# EFR32G13_POWER_RESET.net
KiCad netlist of a schematic drawn in Altium Designer
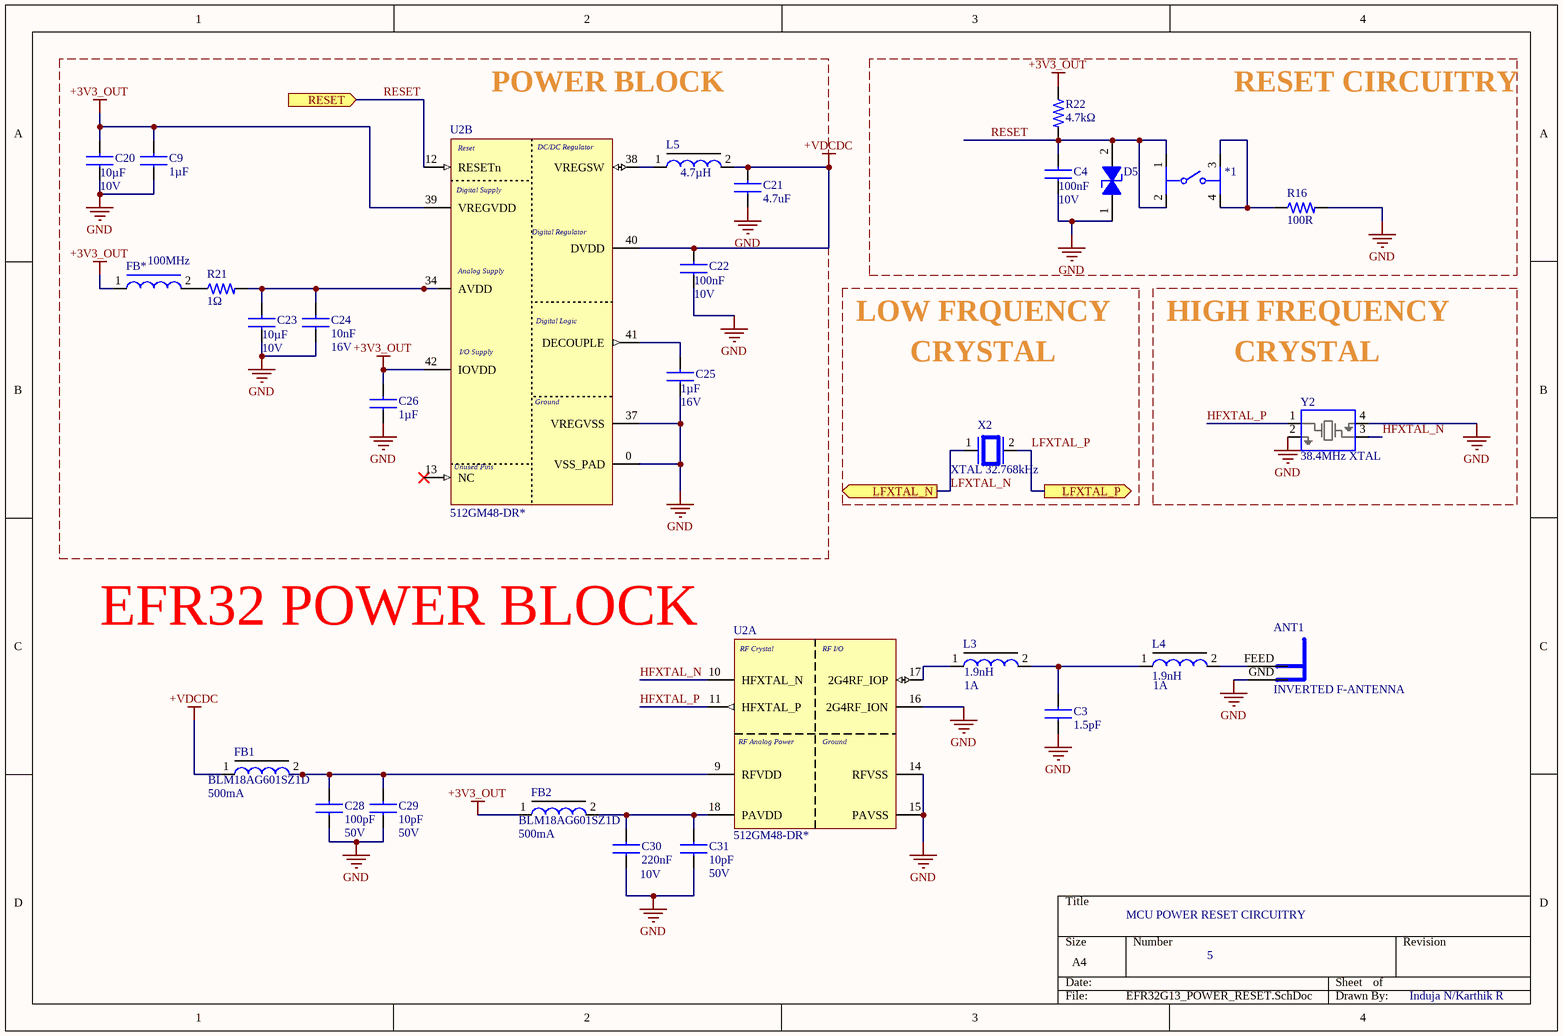
[diagram p0: EFR32G13_POWER_RESET.SchDoc]

(export (version "E")
  (design (tool "Eeschema 10.0.6"))
  (components
    (comp (ref "*1")
      (value "~")
      (footprint "SWITCH")
      (description "Switch Tactile SPST N.O. 0.05A 12VDC 200000Cycles Gull Wing Surface Mount T/R")
      (fields
        (field (name "MANUFACTURER") "C&K Components")
        (field (name "MANUFACTURER PART NUMBER") "PTS526 SK15 SMTR2 LFS")
      )
      (libsource (lib "LPEDT_Components") (part "PTS526 SK15 SMTR2 LFS"))
    )
    (comp (ref "ANT1")
      (value "INVERTED F-ANTENNA")
      (footprint "F_ANTENNA")
      (libsource (lib "LPEDT_Components") (part "INVERTED F-ANTENNA"))
    )
    (comp (ref "C3")
      (value "1.5pF")
      (footprint "Capacitor 0402")
      (fields
        (field (name "MANUFACTURER") "Murata")
        (field (name "MANUFACTURER PART NUMBER") "GJM1555C1H1R5WB01D")
        (field (name "Comment") "CAP 1.5pF 50V 0402")
      )
      (libsource (lib "LPEDT_Components") (part "CAP 1.5pF 50V 0402"))
    )
    (comp (ref "C4")
      (value "100nF")
      (footprint "CAP_0603_1MM")
      (description "0603 0.1 uF 10 V ±10% Tolerance X7R SMT Multilayer Ceramic Chip Capacitor")
      (fields
        (field (name "MANUFACTURER") "Vishay")
        (field (name "MANUFACTURER PART NUMBER") "VJ0603Y104KXQCW1BC")
        (field (name "VOLTAGE RATING (DC)") "10V")
      )
      (libsource (lib "LPEDT_Components") (part "CAP 0.1uF 0603"))
    )
    (comp (ref "C9")
      (value "1µF")
      (footprint "Capacitor 0603")
      (description "16V 1uF X7R ±10% 0603 Multilayer Ceramic Capacitors MLCC - SMD/SMT ROHS")
      (fields
        (field (name "MANUFACTURER") "Samsung Electro-Mechanics")
        (field (name "MANUFACTURER PART NUMBER") "CL10B105KO8NNNC")
      )
      (libsource (lib "LPEDT_Components") (part "CAP 1uF 0603"))
    )
    (comp (ref "C20")
      (value "10µF")
      (footprint "CAP_0603_1MM")
      (description "10V 10uF X7R ±10% 0603 Multilayer Ceramic Capacitors MLCC - SMD/SMT ROHS")
      (fields
        (field (name "MANUFACTURER") "Murata")
        (field (name "MANUFACTURER PART NUMBER") "GRM188Z71A106KA73D")
        (field (name "VOLTAGE RATING") "10V")
      )
      (libsource (lib "LPEDT_Components") (part "CAP 10uF 0603"))
    )
    (comp (ref "C21")
      (value "4.7uF")
      (footprint "CAPC1608X90N")
      (description "4.7 ÂµF Â±10% 16V Ceramic Capacitor X5R 0603 (1608 Metric)")
      (fields (field (name "MF") "Samsung Electro-Mechanics") (field (name "MP") "CL10A475KO8NNNC"))
      (libsource (lib "LPEDT_Components") (part "CAP 4.7uF 16V 0603"))
    )
    (comp (ref "C22")
      (value "100nF")
      (footprint "CAP_0603_1MM")
      (description "0603 0.1 uF 10 V ±10% Tolerance X7R SMT Multilayer Ceramic Chip Capacitor")
      (fields
        (field (name "MANUFACTURER") "Vishay")
        (field (name "MANUFACTURER PART NUMBER") "VJ0603Y104KXQCW1BC")
        (field (name "VOLTAGE RATING (DC)") "10V")
      )
      (libsource (lib "LPEDT_Components") (part "CAP 0.1uF 0603"))
    )
    (comp (ref "C23")
      (value "10µF")
      (footprint "CAP_0603_1MM")
      (description "10V 10uF X7R ±10% 0603 Multilayer Ceramic Capacitors MLCC - SMD/SMT ROHS")
      (fields
        (field (name "MANUFACTURER") "Murata")
        (field (name "MANUFACTURER PART NUMBER") "GRM188Z71A106KA73D")
        (field (name "VOLTAGE RATING") "10V")
      )
      (libsource (lib "LPEDT_Components") (part "CAP 10uF 0603"))
    )
    (comp (ref "C24")
      (value "10nF")
      (footprint "Capacitor 0603")
      (description "Multilayer Ceramic Capacitors MLCC - SMD/SMT 16V 0.01uF X7R 0603 10% AEC-Q200")
      (fields
        (field (name "MANUFACTURER") "KEMET")
        (field (name "MANUFACTURER PART NUMBER") "C0603C103K4RECAUTO")
        (field (name "VOLTAGE RATING (DC)") "16V")
      )
      (libsource (lib "LPEDT_Components") (part "CAP 10nF 0603"))
    )
    (comp (ref "C25")
      (value "1µF")
      (footprint "Capacitor 0603")
      (description "16V 1uF X7R ±10% 0603 Multilayer Ceramic Capacitors MLCC - SMD/SMT ROHS")
      (fields
        (field (name "MANUFACTURER") "Samsung Electro-Mechanics")
        (field (name "MANUFACTURER PART NUMBER") "CL10B105KO8NNNC")
        (field (name "VOLTAGE RATING (DC)") "16V")
      )
      (libsource (lib "LPEDT_Components") (part "CAP 1uF 0603"))
    )
    (comp (ref "C26")
      (value "1µF")
      (footprint "Capacitor 0603")
      (description "16V 1uF X7R ±10% 0603 Multilayer Ceramic Capacitors MLCC - SMD/SMT ROHS")
      (fields
        (field (name "MANUFACTURER") "Samsung Electro-Mechanics")
        (field (name "MANUFACTURER PART NUMBER") "CL10B105KO8NNNC")
      )
      (libsource (lib "LPEDT_Components") (part "CAP 1uF 0603"))
    )
    (comp (ref "C28")
      (value "100pF")
      (footprint "CAP_0603_1MM")
      (description "50V 100pF NP0 ±5% 0603 Multilayer Ceramic Capacitors MLCC - SMD/SMT ROHS")
      (fields
        (field (name "MANUFACTURER") "Yageo Group")
        (field (name "MANUFACTURER PART NUMBER") "CC0603JRNPO9BN101")
        (field (name "VOLTAGE RATING (DC)") "50V")
      )
      (libsource (lib "LPEDT_Components") (part "CAP 100pF 0603"))
    )
    (comp (ref "C29")
      (value "10pF")
      (footprint "Capacitor 0603")
      (fields
        (field (name "MANUFACTURER") "Murata")
        (field (name "MANUFACTURER PART NUMBER") "GRM1555C1H100FA01D")
        (field (name "RATED DC VOLTAGE (URDC)") "50V")
        (field (name "Comment") "CAP 10pF 50V 0603")
      )
      (libsource (lib "LPEDT_Components") (part "CAP 10pF 50V 0603"))
    )
    (comp (ref "C30")
      (value "220nF")
      (footprint "Capacitor 0603")
      (description "0603 0.22 uF 10 V ±10% Tolerance X7R SMT Multilayer Ceramic Capacitor")
      (fields
        (field (name "MANUFACTURER") "Murata")
        (field (name "MANUFACTURER PART NUMBER") "GRM188R71A224KA01J")
        (field (name "VOLTAGE RATING") "10V")
      )
      (libsource (lib "LPEDT_Components") (part "CAP 220nF 10V 0603"))
    )
    (comp (ref "C31")
      (value "10pF")
      (footprint "Capacitor 0603")
      (fields
        (field (name "MANUFACTURER") "Murata")
        (field (name "MANUFACTURER PART NUMBER") "GRM1555C1H100FA01D")
        (field (name "RATED DC VOLTAGE (URDC)") "50V")
        (field (name "Comment") "CAP 10pF 50V 0603")
      )
      (libsource (lib "LPEDT_Components") (part "CAP 10pF 50V 0603"))
    )
    (comp (ref "D5")
      (value "824032815")
      (footprint "WE-TVS_DFN1610-2L")
      (description "824032815 Tvs Diode, Bidir, 5V, Dfn1610 Rohs Compliant: Yes ¦Wurth Elektronik 824032815")
      (libsource (lib "LPEDT_Components") (part "TVS Diode ESD Protection"))
    )
    (comp (ref "FB*")
      (value "BLM21BD102SN1D")
      (footprint "FP-BLM21-0_2-t0_85-e0_5-IPC_A")
      (description "Ferrite Beads Multi-Layer 1KOhm 25% 100MHz 250mA 400mOhm DCR 0805 T/R")
      (fields
        (field (name "MANUFACTURER") "Murata")
        (field (name "CLOCK FREQUENCY") "100MHz")
        (field (name "TOLERANCE") "25%")
      )
      (libsource (lib "LPEDT_Components") (part "BLM21BD102SN1D"))
    )
    (comp (ref "FB1")
      (value "BLM18AG601SZ1D")
      (footprint "Ferrite 0603")
      (description "Chip Ferrite Bead, 0603, 600Ω @ 100MHz, 0.38Ω, 25%, 500mA CMP-06046-002436-1")
      (fields (field (name "MAX CURRENT RATING") "500mA"))
      (libsource (lib "LPEDT_Components") (part "600R Ferrite bead"))
    )
    (comp (ref "FB2")
      (value "BLM18AG601SZ1D")
      (footprint "Ferrite 0603")
      (description "Chip Ferrite Bead, 0603, 600Ω @ 100MHz, 0.38Ω, 25%, 500mA CMP-06046-002436-1")
      (fields (field (name "MAX CURRENT RATING") "500mA"))
      (libsource (lib "LPEDT_Components") (part "600R Ferrite bead"))
    )
    (comp (ref "L3")
      (value "1.9nH")
      (footprint "Ferrite 0402")
      (description "Inductor, 1.9Nh, 8Ghz, 0402 Rohs Compliant: Yes ¦Murata LQG15WZ1N9S02D")
      (fields
        (field (name "MANUFACTURER") "Murata")
        (field (name "MANUFACTURER PART NUMBER") "LQG15WZ1N9S02D")
        (field (name "CURRENT RATING") "1A")
      )
      (libsource (lib "LPEDT_Components") (part "IND 1.9nH"))
    )
    (comp (ref "L4")
      (value "1.9nH")
      (footprint "Ferrite 0402")
      (description "Inductor, 1.9Nh, 8Ghz, 0402 Rohs Compliant: Yes ¦Murata LQG15WZ1N9S02D")
      (fields
        (field (name "MANUFACTURER") "Murata")
        (field (name "MANUFACTURER PART NUMBER") "LQG15WZ1N9S02D")
        (field (name "CURRENT RATING") "1A")
      )
      (libsource (lib "LPEDT_Components") (part "IND 1.9nH"))
    )
    (comp (ref "L5")
      (value "4.7µH")
      (footprint "Capacitor 0603")
      (description "Inductor Power Shielded Multi-Layer 4.7uH 20% 2MHz Ferrite 0.12A 0.65Ohm DCR 0603 T/R")
      (fields
        (field (name "MANUFACTURER") "TDK")
        (field (name "MANUFACTURER PART NUMBER") "MLZ1608M4R7WT000")
      )
      (libsource (lib "LPEDT_Components") (part "IND 4.7uH"))
    )
    (comp (ref "R16")
      (value "100R")
      (footprint "RES_0603_1608X06")
      (fields
        (field (name "MANUFACTURER") "Yageo")
        (field (name "MANUFACTURER PART NUMBER") "RC0603FR-07100RL")
        (field (name "TOLERANCE") "1%")
      )
      (libsource (lib "LPEDT_Components") (part "RES 100R 0603"))
    )
    (comp (ref "R21")
      (value "1Ω")
      (footprint "RES_0603_1608X06")
      (fields
        (field (name "MANUFACTURER") "Yageo")
        (field (name "MANUFACTURER PART NUMBER") "RC0603FR-074K7L")
        (field (name "TOLERANCE") "1%")
      )
      (libsource (lib "LPEDT_Components") (part "RES 1Ohm 0603"))
    )
    (comp (ref "R22")
      (value "4.7kΩ")
      (footprint "RES_0603_1608X06")
      (fields
        (field (name "MANUFACTURER") "Yageo")
        (field (name "MANUFACTURER PART NUMBER") "RC0603FR-074K7L")
        (field (name "TOLERANCE") "1%")
      )
      (libsource (lib "LPEDT_Components") (part "RES 4.7K 0603"))
    )
    (comp (ref "U2")
      (value "512GM48-DR*")
      (footprint "QFN_48_7x7")
      (description "Blue Gecko QFN48 2.4 G 19 dB BLE/Proprietary 512 kB 64 kB(RAM) 31GPIO")
      (fields
        (field (name "MANUFACTURER") "Silicon Labs")
        (field (name "MANUFACTURER PART NUMBER") "EFR32BG13P732F512GM48-DR")
      )
      (libsource (lib "LPEDT_Components") (part "EFR32BG13P732F512GM48-DR"))
    )
    (comp (ref "X2")
      (value "XTAL 32.768kHz")
      (footprint "XTAL_32.768KHZ-T")
      (description "Crystal 0.032768MHz ±20ppm (Tol) 12.5pF Flexural 70000Ohm 2-Pin CSMD T/R")
      (fields
        (field (name "MANUFACTURER") "Abracon")
        (field (name "MANUFACTURER PART NUMBER") "ABS07-32.768KHZ-H-T")
      )
      (libsource (lib "LPEDT_Components") (part "XTAL 32.768kHz"))
    )
    (comp (ref "Y2")
      (value "38.4MHz XTAL")
      (footprint "XTAL 38.4MHz")
      (description "Fundamental Active RoHS Compliant MHz Crystal Crystal 10pF 0.022 0.55mm -20C~70C 80Ohm")
      (fields (field (name "MANUFACTURER") "TXC") (field (name "MANUFACTURER PART NUMBER") "8Y38472012"))
      (libsource (lib "LPEDT_Components") (part "38.4MHz XTAL"))
    )
  )
  (nets
    (net (code "1") (name "+3V3_OUT") (class "Default")
      (node (ref "C20") (pin "1") (pinfunction "1_1") (pintype "passive"))
      (node (ref "C26") (pin "1") (pinfunction "1_1") (pintype "passive"))
      (node (ref "C9") (pin "1") (pinfunction "1_1") (pintype "passive"))
      (node (ref "FB*") (pin "1") (pinfunction "1_1") (pintype "passive"))
      (node (ref "FB2") (pin "1") (pinfunction "1_1") (pintype "passive"))
      (node (ref "R22") (pin "1") (pinfunction "1_1") (pintype "passive"))
      (node (ref "U2") (pin "39") (pinfunction "VREGVDD_39") (pintype "power_in"))
      (node (ref "U2") (pin "42") (pinfunction "IOVDD_42") (pintype "power_in"))
    )
    (net (code "2") (name "+VDCDC") (class "Default")
      (node (ref "C21") (pin "1") (pinfunction "1_1") (pintype "passive"))
      (node (ref "C22") (pin "1") (pinfunction "1_1") (pintype "passive"))
      (node (ref "FB1") (pin "1") (pinfunction "1_1") (pintype "passive"))
      (node (ref "L5") (pin "2") (pinfunction "2_2") (pintype "passive"))
      (node (ref "U2") (pin "40") (pinfunction "DVDD_40") (pintype "power_in"))
    )
    (net (code "3") (name "/HFXTAL_N") (class "Default")
      (node (ref "U2") (pin "10") (pinfunction "HFXTAL_N_10") (pintype "input"))
      (node (ref "Y2") (pin "3") (pinfunction "3_3") (pintype "passive"))
    )
    (net (code "4") (name "/HFXTAL_P") (class "Default")
      (node (ref "U2") (pin "11") (pinfunction "HFXTAL_P_11") (pintype "output"))
      (node (ref "Y2") (pin "1") (pinfunction "1_1") (pintype "passive"))
    )
    (net (code "5") (name "/LFXTAL_N") (class "Default")
      (node (ref "X2") (pin "1") (pinfunction "1_1") (pintype "passive"))
    )
    (net (code "6") (name "/LFXTAL_P") (class "Default")
      (node (ref "X2") (pin "2") (pinfunction "2_2") (pintype "passive"))
    )
    (net (code "7") (name "/RESET") (class "Default")
      (node (ref "*1") (pin "1") (pinfunction "1_1") (pintype "passive"))
      (node (ref "*1") (pin "2") (pinfunction "2_2") (pintype "passive"))
      (node (ref "C4") (pin "1") (pinfunction "1_1") (pintype "passive"))
      (node (ref "D5") (pin "2") (pinfunction "GND_2") (pintype "passive"))
      (node (ref "R22") (pin "2") (pinfunction "2_2") (pintype "passive"))
      (node (ref "U2") (pin "12") (pinfunction "RESETn_12") (pintype "input"))
    )
    (net (code "8") (name "GND") (class "Default")
      (node (ref "ANT1") (pin "GND") (pinfunction "GND_GND") (pintype "power_in"))
      (node (ref "C20") (pin "2") (pinfunction "2_2") (pintype "passive"))
      (node (ref "C21") (pin "2") (pinfunction "2_2") (pintype "passive"))
      (node (ref "C22") (pin "2") (pinfunction "2_2") (pintype "passive"))
      (node (ref "C23") (pin "2") (pinfunction "2_2") (pintype "passive"))
      (node (ref "C24") (pin "2") (pinfunction "2_2") (pintype "passive"))
      (node (ref "C25") (pin "2") (pinfunction "2_2") (pintype "passive"))
      (node (ref "C26") (pin "2") (pinfunction "2_2") (pintype "passive"))
      (node (ref "C28") (pin "2") (pinfunction "2_2") (pintype "passive"))
      (node (ref "C29") (pin "2") (pinfunction "2_2") (pintype "passive"))
      (node (ref "C3") (pin "2") (pinfunction "2_2") (pintype "passive"))
      (node (ref "C30") (pin "2") (pinfunction "2_2") (pintype "passive"))
      (node (ref "C31") (pin "2") (pinfunction "2_2") (pintype "passive"))
      (node (ref "C4") (pin "2") (pinfunction "2_2") (pintype "passive"))
      (node (ref "C9") (pin "2") (pinfunction "2_2") (pintype "passive"))
      (node (ref "D5") (pin "1") (pinfunction "I/O_1_1") (pintype "passive"))
      (node (ref "R16") (pin "2") (pinfunction "2_2") (pintype "passive"))
      (node (ref "U2") (pin "0") (pinfunction "VSS_PAD_0") (pintype "power_in"))
      (node (ref "U2") (pin "14") (pinfunction "RFVSS_14") (pintype "power_in"))
      (node (ref "U2") (pin "15") (pinfunction "PAVSS_15") (pintype "power_in"))
      (node (ref "U2") (pin "16") (pinfunction "2G4RF_ION_16") (pintype "bidirectional"))
      (node (ref "U2") (pin "37") (pinfunction "VREGVSS_37") (pintype "power_in"))
      (node (ref "Y2") (pin "2") (pinfunction "2_2") (pintype "passive"))
      (node (ref "Y2") (pin "4") (pinfunction "4_4") (pintype "passive"))
    )
    (net (code "9") (name "Net-(*1-Pad3)") (class "Default")
      (node (ref "*1") (pin "3") (pinfunction "3_3") (pintype "passive"))
      (node (ref "*1") (pin "4") (pinfunction "4_4") (pintype "passive"))
      (node (ref "R16") (pin "1") (pinfunction "1_1") (pintype "passive"))
    )
    (net (code "10") (name "Net-(ANT1-PadFEED)") (class "Default")
      (node (ref "ANT1") (pin "FEED") (pinfunction "FEED_FEED") (pintype "passive"))
      (node (ref "L4") (pin "2") (pinfunction "2_2") (pintype "passive"))
    )
    (net (code "11") (name "Net-(C3-Pad1)") (class "Default")
      (node (ref "C3") (pin "1") (pinfunction "1_1") (pintype "passive"))
      (node (ref "L3") (pin "2") (pinfunction "2_2") (pintype "passive"))
      (node (ref "L4") (pin "1") (pinfunction "1_1") (pintype "passive"))
    )
    (net (code "12") (name "Net-(FB*-Pad2)") (class "Default")
      (node (ref "FB*") (pin "2") (pinfunction "2_2") (pintype "passive"))
      (node (ref "R21") (pin "1") (pinfunction "1_1") (pintype "passive"))
    )
    (net (code "13") (name "Net-(U2A-2G4RF_IOP)") (class "Default")
      (node (ref "L3") (pin "1") (pinfunction "1_1") (pintype "passive"))
      (node (ref "U2") (pin "17") (pinfunction "2G4RF_IOP_17") (pintype "bidirectional"))
    )
    (net (code "14") (name "Net-(U2A-PAVDD)") (class "Default")
      (node (ref "C30") (pin "1") (pinfunction "1_1") (pintype "passive"))
      (node (ref "C31") (pin "1") (pinfunction "1_1") (pintype "passive"))
      (node (ref "FB2") (pin "2") (pinfunction "2_2") (pintype "passive"))
      (node (ref "U2") (pin "18") (pinfunction "PAVDD_18") (pintype "power_in"))
    )
    (net (code "15") (name "Net-(U2A-RFVDD)") (class "Default")
      (node (ref "C28") (pin "1") (pinfunction "1_1") (pintype "passive"))
      (node (ref "C29") (pin "1") (pinfunction "1_1") (pintype "passive"))
      (node (ref "FB1") (pin "2") (pinfunction "2_2") (pintype "passive"))
      (node (ref "U2") (pin "9") (pinfunction "RFVDD_9") (pintype "power_in"))
    )
    (net (code "16") (name "Net-(U2B-AVDD)") (class "Default")
      (node (ref "C23") (pin "1") (pinfunction "1_1") (pintype "passive"))
      (node (ref "C24") (pin "1") (pinfunction "1_1") (pintype "passive"))
      (node (ref "R21") (pin "2") (pinfunction "2_2") (pintype "passive"))
      (node (ref "U2") (pin "34") (pinfunction "AVDD_34") (pintype "power_in"))
    )
    (net (code "17") (name "Net-(U2B-DECOUPLE)") (class "Default")
      (node (ref "C25") (pin "1") (pinfunction "1_1") (pintype "passive"))
      (node (ref "U2") (pin "41") (pinfunction "DECOUPLE_41") (pintype "output"))
    )
    (net (code "18") (name "Net-(U2B-VREGSW)") (class "Default")
      (node (ref "L5") (pin "1") (pinfunction "1_1") (pintype "passive"))
      (node (ref "U2") (pin "38") (pinfunction "VREGSW_38") (pintype "bidirectional"))
    )
    (net (code "19") (name "unconnected-(U2B-NC-Pad13)") (class "Default")
      (node (ref "U2") (pin "13") (pinfunction "NC_13") (pintype "input+no_connect"))
    )
  )
)
